# DfMUX_Transceiver.net
KiCad netlist of a schematic drawn in Altium Designer
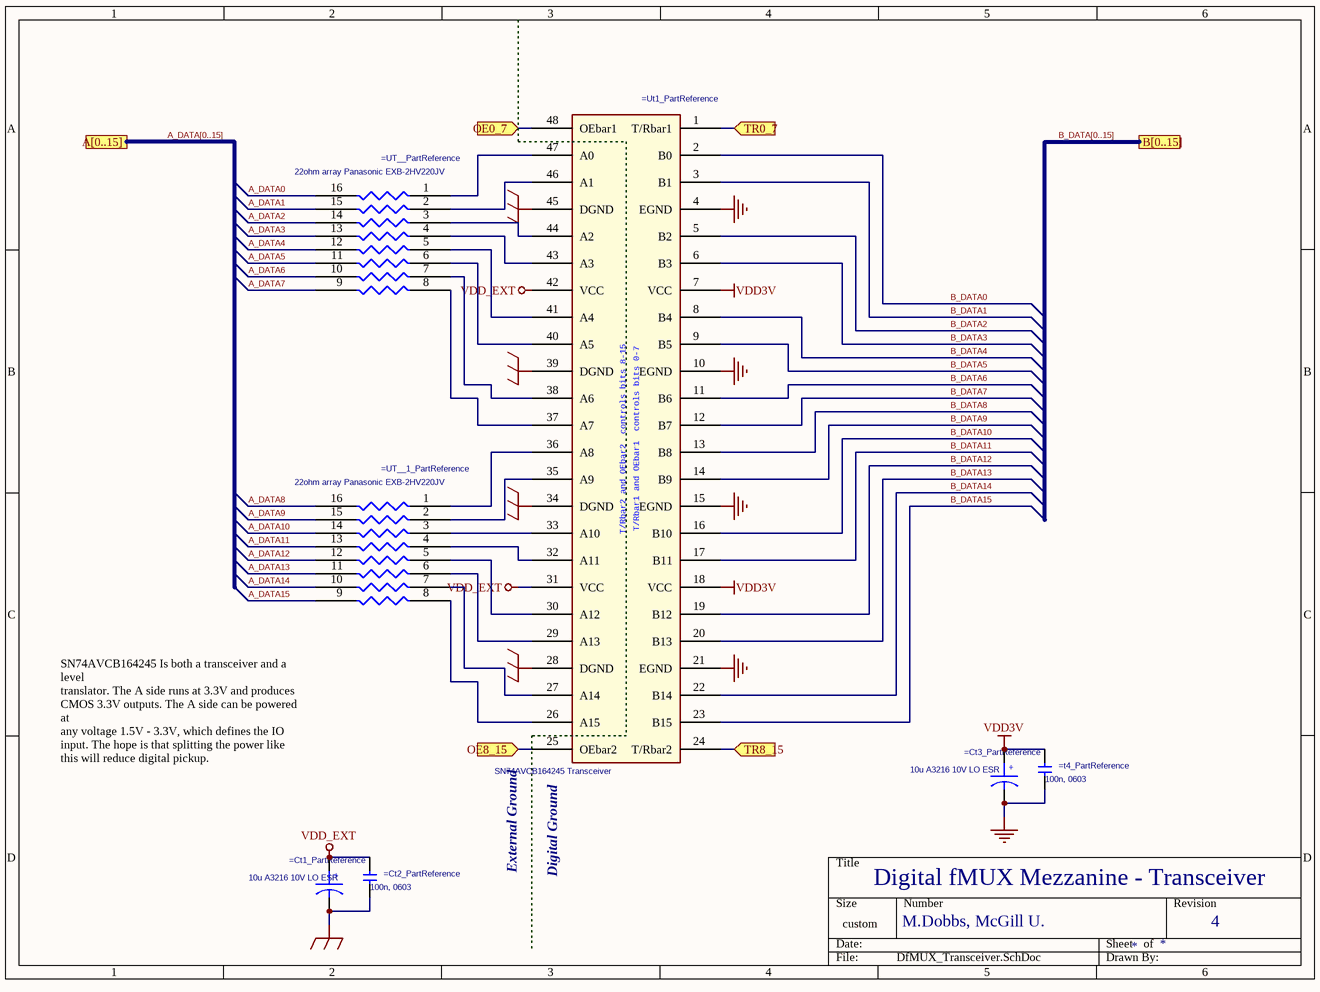
[diagram p0: DfMUX_Transceiver.SchDoc]

(export (version "E")
  (design (tool "Eeschema 10.0.6"))
  (components
    (comp (ref "=Ct1_PartReference")
      (value "10u A3216 10V LO ESR")
      (libsource (lib "*") (part "CAPACITOR POL"))
    )
    (comp (ref "=Ct2_PartReference")
      (value "100n, 0603")
      (footprint "0603C")
      (libsource (lib "*") (part "C"))
    )
    (comp (ref "=Ct3_PartReference")
      (value "10u A3216 10V LO ESR")
      (libsource (lib "*") (part "CAPACITOR POL"))
    )
    (comp (ref "=t4_PartReference") (value "100n, 0603") (footprint "0603C") (libsource (lib "*") (part "C")))
    (comp (ref "=Ut1_PartReference")
      (value "SN74AVCB164245 Transceiver")
      (libsource (lib "*") (part "74LVT16245 Transceiver_0"))
    )
    (comp (ref "=UT__1_PartReference")
      (value "22ohm array Panasonic EXB-2HV220JV")
      (libsource (lib "*") (part "R-PACK"))
    )
    (comp (ref "=UT__PartReference")
      (value "22ohm array Panasonic EXB-2HV220JV")
      (libsource (lib "*") (part "R-PACK"))
    )
  )
  (nets
    (net (code "1") (name "/A_DATA0") (class "Default")
      (node (ref "=UT__PartReference") (pin "16") (pinfunction "R1_16") (pintype "passive"))
    )
    (net (code "2") (name "/A_DATA1") (class "Default")
      (node (ref "=UT__PartReference") (pin "15") (pinfunction "R2_15") (pintype "passive"))
    )
    (net (code "3") (name "/A_DATA2") (class "Default")
      (node (ref "=UT__PartReference") (pin "14") (pinfunction "R3_14") (pintype "passive"))
    )
    (net (code "4") (name "/A_DATA3") (class "Default")
      (node (ref "=UT__PartReference") (pin "13") (pinfunction "R4_13") (pintype "passive"))
    )
    (net (code "5") (name "/A_DATA4") (class "Default")
      (node (ref "=UT__PartReference") (pin "12") (pinfunction "R5_12") (pintype "passive"))
    )
    (net (code "6") (name "/A_DATA5") (class "Default")
      (node (ref "=UT__PartReference") (pin "11") (pinfunction "R6_11") (pintype "passive"))
    )
    (net (code "7") (name "/A_DATA6") (class "Default")
      (node (ref "=UT__PartReference") (pin "10") (pinfunction "R7_10") (pintype "passive"))
    )
    (net (code "8") (name "/A_DATA7") (class "Default")
      (node (ref "=UT__PartReference") (pin "9") (pinfunction "R8_9") (pintype "passive"))
    )
    (net (code "9") (name "/A_DATA8") (class "Default")
      (node (ref "=UT__1_PartReference") (pin "16") (pinfunction "R1_16") (pintype "passive"))
    )
    (net (code "10") (name "/A_DATA9") (class "Default")
      (node (ref "=UT__1_PartReference") (pin "15") (pinfunction "R2_15") (pintype "passive"))
    )
    (net (code "11") (name "/A_DATA10") (class "Default")
      (node (ref "=UT__1_PartReference") (pin "14") (pinfunction "R3_14") (pintype "passive"))
    )
    (net (code "12") (name "/A_DATA11") (class "Default")
      (node (ref "=UT__1_PartReference") (pin "13") (pinfunction "R4_13") (pintype "passive"))
    )
    (net (code "13") (name "/A_DATA12") (class "Default")
      (node (ref "=UT__1_PartReference") (pin "12") (pinfunction "R5_12") (pintype "passive"))
    )
    (net (code "14") (name "/A_DATA13") (class "Default")
      (node (ref "=UT__1_PartReference") (pin "11") (pinfunction "R6_11") (pintype "passive"))
    )
    (net (code "15") (name "/A_DATA14") (class "Default")
      (node (ref "=UT__1_PartReference") (pin "10") (pinfunction "R7_10") (pintype "passive"))
    )
    (net (code "16") (name "/A_DATA15") (class "Default")
      (node (ref "=UT__1_PartReference") (pin "9") (pinfunction "R8_9") (pintype "passive"))
    )
    (net (code "18") (name "/B_DATA0") (class "Default")
      (node (ref "=Ut1_PartReference") (pin "2") (pinfunction "B0_2") (pintype "passive"))
    )
    (net (code "19") (name "/B_DATA1") (class "Default")
      (node (ref "=Ut1_PartReference") (pin "3") (pinfunction "B1_3") (pintype "passive"))
    )
    (net (code "20") (name "/B_DATA2") (class "Default")
      (node (ref "=Ut1_PartReference") (pin "5") (pinfunction "B2_5") (pintype "passive"))
    )
    (net (code "21") (name "/B_DATA3") (class "Default")
      (node (ref "=Ut1_PartReference") (pin "6") (pinfunction "B3_6") (pintype "passive"))
    )
    (net (code "22") (name "/B_DATA4") (class "Default")
      (node (ref "=Ut1_PartReference") (pin "8") (pinfunction "B4_8") (pintype "passive"))
    )
    (net (code "23") (name "/B_DATA5") (class "Default")
      (node (ref "=Ut1_PartReference") (pin "9") (pinfunction "B5_9") (pintype "passive"))
    )
    (net (code "24") (name "/B_DATA6") (class "Default")
      (node (ref "=Ut1_PartReference") (pin "11") (pinfunction "B6_11") (pintype "passive"))
    )
    (net (code "25") (name "/B_DATA7") (class "Default")
      (node (ref "=Ut1_PartReference") (pin "12") (pinfunction "B7_12") (pintype "passive"))
    )
    (net (code "26") (name "/B_DATA8") (class "Default")
      (node (ref "=Ut1_PartReference") (pin "13") (pinfunction "B8_13") (pintype "passive"))
    )
    (net (code "27") (name "/B_DATA9") (class "Default")
      (node (ref "=Ut1_PartReference") (pin "14") (pinfunction "B9_14") (pintype "passive"))
    )
    (net (code "28") (name "/B_DATA10") (class "Default")
      (node (ref "=Ut1_PartReference") (pin "16") (pinfunction "B10_16") (pintype "passive"))
    )
    (net (code "29") (name "/B_DATA11") (class "Default")
      (node (ref "=Ut1_PartReference") (pin "17") (pinfunction "B11_17") (pintype "passive"))
    )
    (net (code "30") (name "/B_DATA12") (class "Default")
      (node (ref "=Ut1_PartReference") (pin "19") (pinfunction "B12_19") (pintype "passive"))
    )
    (net (code "31") (name "/B_DATA13") (class "Default")
      (node (ref "=Ut1_PartReference") (pin "20") (pinfunction "B13_20") (pintype "passive"))
    )
    (net (code "32") (name "/B_DATA14") (class "Default")
      (node (ref "=Ut1_PartReference") (pin "22") (pinfunction "B14_22") (pintype "passive"))
    )
    (net (code "33") (name "/B_DATA15") (class "Default")
      (node (ref "=Ut1_PartReference") (pin "23") (pinfunction "B15_23") (pintype "passive"))
    )
    (net (code "35") (name "/OE0_7") (class "Default")
      (node (ref "=Ut1_PartReference") (pin "48") (pinfunction "OEbar1_48") (pintype "passive"))
    )
    (net (code "36") (name "/OE8_15") (class "Default")
      (node (ref "=Ut1_PartReference") (pin "25") (pinfunction "OEbar2_25") (pintype "passive"))
    )
    (net (code "37") (name "/TR0_7") (class "Default")
      (node (ref "=Ut1_PartReference") (pin "1") (pinfunction "T/Rbar1_1") (pintype "passive"))
    )
    (net (code "38") (name "/TR8_15") (class "Default")
      (node (ref "=Ut1_PartReference") (pin "24") (pinfunction "T/Rbar2_24") (pintype "passive"))
    )
    (net (code "39") (name "GND_DIG") (class "Default")
      (node (ref "=Ct3_PartReference") (pin "2") (pinfunction "2_2") (pintype "passive"))
      (node (ref "=Ut1_PartReference") (pin "10") (pinfunction "EGND_10") (pintype "passive"))
      (node (ref "=Ut1_PartReference") (pin "15") (pinfunction "EGND_15") (pintype "passive"))
      (node (ref "=Ut1_PartReference") (pin "21") (pinfunction "EGND_21") (pintype "passive"))
      (node (ref "=Ut1_PartReference") (pin "4") (pinfunction "EGND_4") (pintype "passive"))
      (node (ref "=t4_PartReference") (pin "1") (pinfunction "1_1") (pintype "passive"))
    )
    (net (code "40") (name "GND_EARTH") (class "Default")
      (node (ref "=Ct1_PartReference") (pin "2") (pinfunction "2_2") (pintype "passive"))
      (node (ref "=Ct2_PartReference") (pin "1") (pinfunction "1_1") (pintype "passive"))
      (node (ref "=Ut1_PartReference") (pin "28") (pinfunction "DGND_28") (pintype "passive"))
      (node (ref "=Ut1_PartReference") (pin "34") (pinfunction "DGND_34") (pintype "passive"))
      (node (ref "=Ut1_PartReference") (pin "39") (pinfunction "DGND_39") (pintype "passive"))
      (node (ref "=Ut1_PartReference") (pin "45") (pinfunction "DGND_45") (pintype "passive"))
    )
    (net (code "41") (name "Net-(=Ut1_PartReference-A0)") (class "Default")
      (node (ref "=UT__PartReference") (pin "1") (pinfunction "R1_1") (pintype "passive"))
      (node (ref "=Ut1_PartReference") (pin "47") (pinfunction "A0_47") (pintype "passive"))
    )
    (net (code "42") (name "Net-(=Ut1_PartReference-A1)") (class "Default")
      (node (ref "=UT__PartReference") (pin "2") (pinfunction "R2_2") (pintype "passive"))
      (node (ref "=Ut1_PartReference") (pin "46") (pinfunction "A1_46") (pintype "passive"))
    )
    (net (code "43") (name "Net-(=Ut1_PartReference-A2)") (class "Default")
      (node (ref "=UT__PartReference") (pin "3") (pinfunction "R3_3") (pintype "passive"))
      (node (ref "=Ut1_PartReference") (pin "44") (pinfunction "A2_44") (pintype "passive"))
    )
    (net (code "44") (name "Net-(=Ut1_PartReference-A3)") (class "Default")
      (node (ref "=UT__PartReference") (pin "4") (pinfunction "R4_4") (pintype "passive"))
      (node (ref "=Ut1_PartReference") (pin "43") (pinfunction "A3_43") (pintype "passive"))
    )
    (net (code "45") (name "Net-(=Ut1_PartReference-A4)") (class "Default")
      (node (ref "=UT__PartReference") (pin "5") (pinfunction "R5_5") (pintype "passive"))
      (node (ref "=Ut1_PartReference") (pin "41") (pinfunction "A4_41") (pintype "passive"))
    )
    (net (code "46") (name "Net-(=Ut1_PartReference-A5)") (class "Default")
      (node (ref "=UT__PartReference") (pin "6") (pinfunction "R6_6") (pintype "passive"))
      (node (ref "=Ut1_PartReference") (pin "40") (pinfunction "A5_40") (pintype "passive"))
    )
    (net (code "47") (name "Net-(=Ut1_PartReference-A6)") (class "Default")
      (node (ref "=UT__PartReference") (pin "7") (pinfunction "R7_7") (pintype "passive"))
      (node (ref "=Ut1_PartReference") (pin "38") (pinfunction "A6_38") (pintype "passive"))
    )
    (net (code "48") (name "Net-(=Ut1_PartReference-A7)") (class "Default")
      (node (ref "=UT__PartReference") (pin "8") (pinfunction "R8_8") (pintype "passive"))
      (node (ref "=Ut1_PartReference") (pin "37") (pinfunction "A7_37") (pintype "passive"))
    )
    (net (code "49") (name "Net-(=Ut1_PartReference-A8)") (class "Default")
      (node (ref "=UT__1_PartReference") (pin "1") (pinfunction "R1_1") (pintype "passive"))
      (node (ref "=Ut1_PartReference") (pin "36") (pinfunction "A8_36") (pintype "passive"))
    )
    (net (code "50") (name "Net-(=Ut1_PartReference-A9)") (class "Default")
      (node (ref "=UT__1_PartReference") (pin "2") (pinfunction "R2_2") (pintype "passive"))
      (node (ref "=Ut1_PartReference") (pin "35") (pinfunction "A9_35") (pintype "passive"))
    )
    (net (code "51") (name "Net-(=Ut1_PartReference-A10)") (class "Default")
      (node (ref "=UT__1_PartReference") (pin "3") (pinfunction "R3_3") (pintype "passive"))
      (node (ref "=Ut1_PartReference") (pin "33") (pinfunction "A10_33") (pintype "passive"))
    )
    (net (code "52") (name "Net-(=Ut1_PartReference-A11)") (class "Default")
      (node (ref "=UT__1_PartReference") (pin "4") (pinfunction "R4_4") (pintype "passive"))
      (node (ref "=Ut1_PartReference") (pin "32") (pinfunction "A11_32") (pintype "passive"))
    )
    (net (code "53") (name "Net-(=Ut1_PartReference-A12)") (class "Default")
      (node (ref "=UT__1_PartReference") (pin "5") (pinfunction "R5_5") (pintype "passive"))
      (node (ref "=Ut1_PartReference") (pin "30") (pinfunction "A12_30") (pintype "passive"))
    )
    (net (code "54") (name "Net-(=Ut1_PartReference-A13)") (class "Default")
      (node (ref "=UT__1_PartReference") (pin "6") (pinfunction "R6_6") (pintype "passive"))
      (node (ref "=Ut1_PartReference") (pin "29") (pinfunction "A13_29") (pintype "passive"))
    )
    (net (code "55") (name "Net-(=Ut1_PartReference-A14)") (class "Default")
      (node (ref "=UT__1_PartReference") (pin "7") (pinfunction "R7_7") (pintype "passive"))
      (node (ref "=Ut1_PartReference") (pin "27") (pinfunction "A14_27") (pintype "passive"))
    )
    (net (code "56") (name "Net-(=Ut1_PartReference-A15)") (class "Default")
      (node (ref "=UT__1_PartReference") (pin "8") (pinfunction "R8_8") (pintype "passive"))
      (node (ref "=Ut1_PartReference") (pin "26") (pinfunction "A15_26") (pintype "passive"))
    )
    (net (code "57") (name "VDD3V") (class "Default")
      (node (ref "=Ct3_PartReference") (pin "1") (pinfunction "1_1") (pintype "passive"))
      (node (ref "=Ut1_PartReference") (pin "18") (pinfunction "VCC_18") (pintype "passive"))
      (node (ref "=Ut1_PartReference") (pin "7") (pinfunction "VCC_7") (pintype "passive"))
      (node (ref "=t4_PartReference") (pin "2") (pinfunction "2_2") (pintype "passive"))
    )
    (net (code "58") (name "VDD_EXT") (class "Default")
      (node (ref "=Ct1_PartReference") (pin "1") (pinfunction "1_1") (pintype "passive"))
      (node (ref "=Ct2_PartReference") (pin "2") (pinfunction "2_2") (pintype "passive"))
      (node (ref "=Ut1_PartReference") (pin "31") (pinfunction "VCC_31") (pintype "passive"))
      (node (ref "=Ut1_PartReference") (pin "42") (pinfunction "VCC_42") (pintype "passive"))
    )
  )
)
